# Sheet.net
KiCad netlist of a schematic drawn in Altium Designer
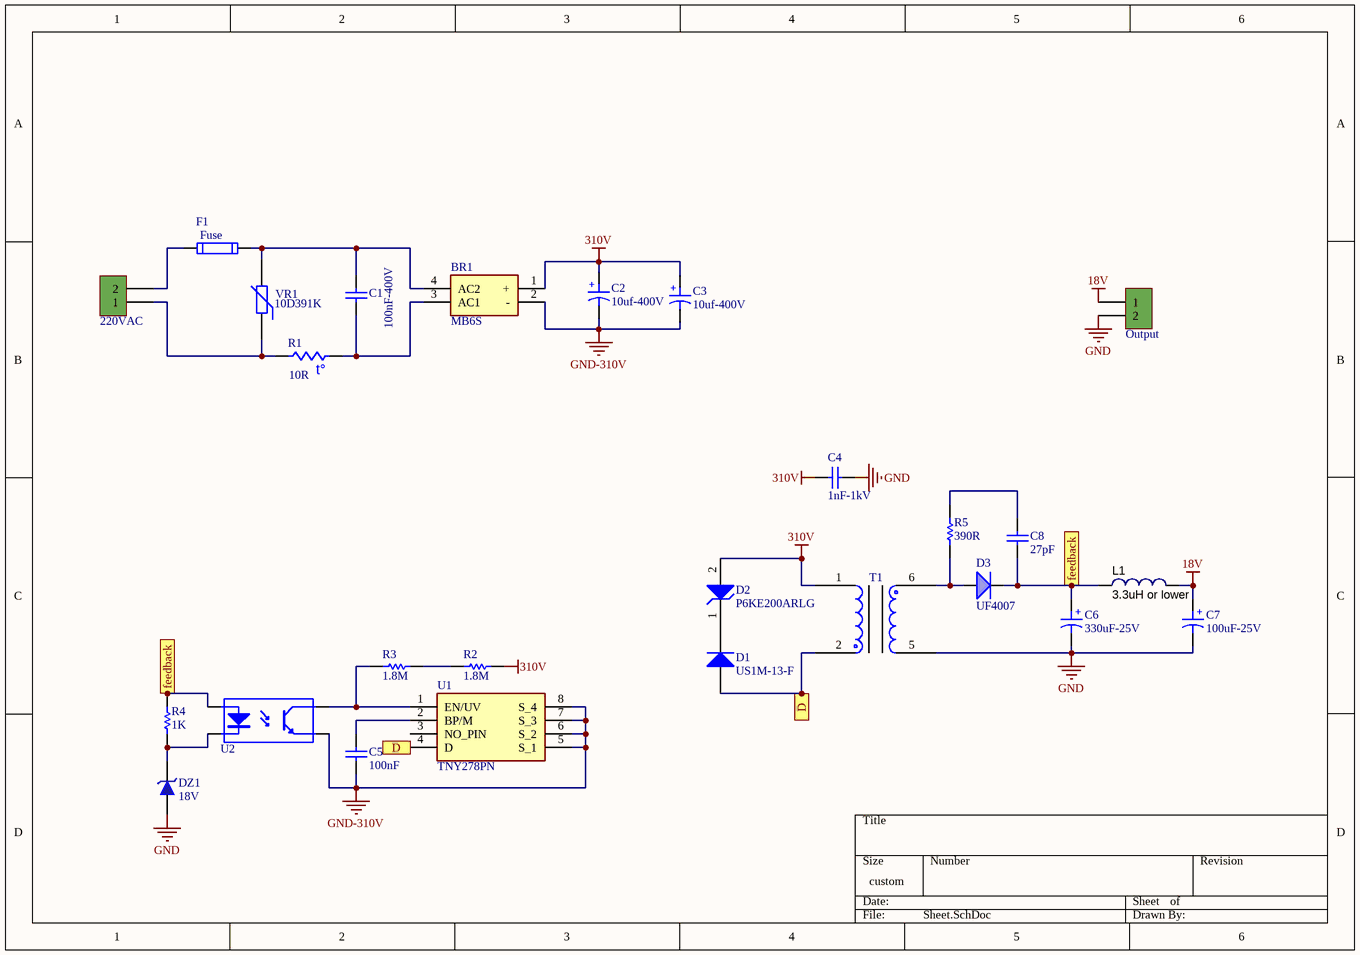
[diagram p0: Sheet.SchDoc]

(export (version "E")
  (design (tool "Eeschema 10.0.6"))
  (components
    (comp (ref "220VAC")
      (value "Phoenix 2 Pin")
      (footprint "Phoenix_2PIN_RA_P5.08mm")
      (libsource (lib "Connector") (part "Phoenix 2 Pin"))
    )
    (comp (ref "BR1")
      (value "MB6S")
      (footprint "SamacSys:SOP250P700X270-4N")
      (description "Bridge Rectifier")
      (libsource (lib "*") (part "MB6S"))
    )
    (comp (ref "C1")
      (value "100nF-400V")
      (footprint "Cap-100nF-400V")
      (description "CAP Ceramic Total")
      (fields (field (name "DESIGNER") "Ali Hafizi"))
      (libsource (lib "Altium") (part "CAP CERAMIC TOTAL SIZE"))
    )
    (comp (ref "C2")
      (value "10uf-400V")
      (footprint "Cap electrolitic radial 10x16-5")
      (description "Cap electrolitic radial")
      (fields (field (name "DESIGNER") "Abbas Basereh"))
      (libsource (lib "Schematic") (part "Cap ELECTROLITIC TOTAL SIZE"))
    )
    (comp (ref "C3")
      (value "10uf-400V")
      (footprint "Cap electrolitic radial 10x16-5")
      (description "Cap electrolitic radial")
      (fields (field (name "DESIGNER") "Abbas Basereh"))
      (libsource (lib "Schematic") (part "Cap ELECTROLITIC TOTAL SIZE"))
    )
    (comp (ref "C4")
      (value "1nF-1kV")
      (footprint "CAP1206")
      (description "TOTAL CAPACITOR SMD PACK")
      (fields (field (name "DESIGNER") "Abbas Basereh"))
      (libsource (lib "Altium") (part "CAP SMD PACKAGE"))
    )
    (comp (ref "C5")
      (value "100nF")
      (footprint "CAP805")
      (description "TOTAL CAPACITOR SMD PACK")
      (fields (field (name "DESIGNER") "Abbas Basereh"))
      (libsource (lib "Altium") (part "CAP SMD PACKAGE"))
    )
    (comp (ref "C6")
      (value "330uF-25V")
      (footprint "Cap electrolitic radial 8x12-3.5")
      (description "Cap electrolitic radial")
      (fields (field (name "DESIGNER") "Abbas Basereh"))
      (libsource (lib "Altium") (part "Cap ELECTROLITIC TOTAL SIZE"))
    )
    (comp (ref "C7")
      (value "100uF-25V")
      (footprint "Cap electrolitic radial 6.3x12-2.5")
      (description "Cap electrolitic radial")
      (fields (field (name "DESIGNER") "Abbas Basereh"))
      (libsource (lib "Altium") (part "Cap ELECTROLITIC TOTAL SIZE"))
    )
    (comp (ref "C8")
      (value "27pF")
      (footprint "CAP805")
      (description "TOTAL CAPACITOR SMD PACK")
      (fields (field (name "DESIGNER") "Abbas Basereh"))
      (libsource (lib "Altium") (part "CAP SMD PACKAGE"))
    )
    (comp (ref "D1")
      (value "US1M-13-F")
      (footprint "DIOD-SMA-2_A_V")
      (description "Ultra-Fast Rectifier, 1 A, 1.7 V, -65 to 150 degC, 2-Pin SMA, RoHS, Tape and Reel")
      (fields (field (name "MANUFACTURER") "Diodes Inc"))
      (libsource (lib "Altium Content Vault") (part "D-AK-2"))
    )
    (comp (ref "D2")
      (value "P6KE200ARLG")
      (footprint "ONSC-SURMETIC40-2-017AA-01")
      (description "600 W Peak Power Transient Voltage Suppressor, 2-Pin Surmetic(TM) 40, Pb-Free, Tape and Reel")
      (fields (field (name "MANUFACTURER") "On Semiconductor"))
      (libsource (lib "Altium Content Vault") (part "ONSC-K1A2-2"))
    )
    (comp (ref "D3")
      (value "UF4007")
      (footprint "DO-41")
      (description "Fast Switching Diodes")
      (fields
        (field (name "MANUFACTURER") "MIC GROUP RECTIFIERS")
        (field (name "MANUFACTURE PART #") "UF4007")
      )
      (libsource (lib "Diode") (part "UF4007"))
    )
    (comp (ref "DZ1")
      (value "18V")
      (footprint "SOD80, LL-34")
      (description "DIODE ZENER GENERAL")
      (fields (field (name "PUBLISHER") "Abbas Basereh"))
      (libsource (lib "Altium") (part "ZENER GENERAL DIODE"))
    )
    (comp (ref "F1")
      (value "FUSE_HOLDER_METAL")
      (footprint "FUSE_5X20MM_4PIN")
      (libsource (lib "Fuse") (part "FUSE METAL 4PIN"))
    )
    (comp (ref "L1")
      (value "3.3uH or lower")
      (footprint "Inductor SMD 3x3.2mm")
      (description "Inductor 4.7µH SMD 3x3.2mm")
      (fields (field (name "TOLERANCE") "±20%"))
      (libsource (lib "Altium") (part "Inductor 4.7µH SMD 3x3.2mm"))
    )
    (comp (ref "Output")
      (value "Phoenix 2 Pin")
      (footprint "Phoenix_2PIN_RA_P5.08mm")
      (libsource (lib "") (part "Phoenix 2 Pin_1"))
    )
    (comp (ref "R1")
      (value "10R")
      (footprint "NTC_9")
      (description "Thick film, SMD chip Resistor")
      (fields (field (name "MANUFACTURE PART #") "NTC10D-9") (field (name "TOLERANCE") "[20%]"))
      (libsource (lib "Resistor") (part "NTC10D-9"))
    )
    (comp (ref "R2")
      (value "1.8M")
      (footprint "RES0805_(2012X06L)")
      (description "TOTAL SMD RESISTOR PACK")
      (fields (field (name "DESIGNER") "Abbas Basereh"))
      (libsource (lib "Altium") (part "RES SMD PACKAGE"))
    )
    (comp (ref "R3")
      (value "1.8M")
      (footprint "RES0805_(2012X06L)")
      (description "TOTAL SMD RESISTOR PACK")
      (fields (field (name "DESIGNER") "Abbas Basereh"))
      (libsource (lib "Altium") (part "RES SMD PACKAGE"))
    )
    (comp (ref "R4")
      (value "1K")
      (footprint "RES0805_(2012X06L)")
      (description "TOTAL SMD RESISTOR PACK")
      (fields (field (name "DESIGNER") "Abbas Basereh"))
      (libsource (lib "Altium") (part "RES SMD PACKAGE"))
    )
    (comp (ref "R5")
      (value "390R")
      (footprint "RES0805_(2012X06L)")
      (description "TOTAL SMD RESISTOR PACK")
      (fields (field (name "DESIGNER") "Abbas Basereh"))
      (libsource (lib "Altium") (part "RES SMD PACKAGE"))
    )
    (comp (ref "T1") (value "EE16-18V") (footprint "EE16-18V") (libsource (lib "EE16-18V") (part "EE16-18V")))
    (comp (ref "U1")
      (value "TNY278PN")
      (footprint "SamacSys:DIP762W56P254L958H406Q8N")
      (description "Integrated Circuit")
      (fields
        (field (name "MANUFACTURER_PART_NUMBER") "TNY274PN")
        (field (name "MOUSER PART NUMBER") "869-TNY274PN")
      )
      (libsource (lib "*") (part "TNY274PN"))
    )
    (comp (ref "U2")
      (value "PC817")
      (footprint "SOP4")
      (description "General Purpose Photocoupler")
      (libsource (lib "Peripheral") (part "PC817"))
    )
    (comp (ref "VR1")
      (value "10D391K")
      (footprint "10D XXX")
      (description "VARISTORS")
      (fields
        (field (name "MANUFACTURER") "china-canada-philipina")
        (field (name "DESIGNER") "Abbas Basereh")
        (field (name "PUBLISHER") "ABBAS BASEREH")
      )
      (libsource (lib "Schematic") (part "VARISTOR (VDR)"))
    )
  )
  (nets
    (net (code "1") (name "/D") (class "Default")
      (node (ref "D1") (pin "1") (pinfunction "A_1") (pintype "passive"))
      (node (ref "T1") (pin "2") (pinfunction "2_2") (pintype "passive"))
      (node (ref "U1") (pin "4") (pinfunction "D_4") (pintype "passive"))
    )
    (net (code "2") (name "/feedback") (class "Default")
      (node (ref "C6") (pin "1") (pinfunction "1_1") (pintype "passive"))
      (node (ref "C8") (pin "1") (pinfunction "1_1") (pintype "passive"))
      (node (ref "D3") (pin "2") (pinfunction "CATHODE_2") (pintype "passive"))
      (node (ref "L1") (pin "1") (pinfunction "1_1") (pintype "passive"))
      (node (ref "R4") (pin "2") (pinfunction "2_2") (pintype "passive"))
      (node (ref "U2") (pin "1") (pinfunction "A_1") (pintype "passive"))
    )
    (net (code "3") (name "18V") (class "Default")
      (node (ref "C7") (pin "1") (pinfunction "1_1") (pintype "passive"))
      (node (ref "L1") (pin "2") (pinfunction "2_2") (pintype "passive"))
      (node (ref "Output") (pin "1") (pinfunction "1_1") (pintype "passive"))
    )
    (net (code "4") (name "310V") (class "Default")
      (node (ref "BR1") (pin "1") (pinfunction "+_1") (pintype "passive"))
      (node (ref "C2") (pin "1") (pinfunction "1_1") (pintype "passive"))
      (node (ref "C3") (pin "1") (pinfunction "1_1") (pintype "passive"))
      (node (ref "C4") (pin "2") (pinfunction "2_2") (pintype "passive"))
      (node (ref "D2") (pin "2") (pinfunction "A_2") (pintype "passive"))
      (node (ref "R2") (pin "2") (pinfunction "2_2") (pintype "passive"))
      (node (ref "T1") (pin "1") (pinfunction "1_1") (pintype "passive"))
    )
    (net (code "5") (name "GND") (class "Default")
      (node (ref "C4") (pin "1") (pinfunction "1_1") (pintype "passive"))
      (node (ref "C6") (pin "2") (pinfunction "2_2") (pintype "passive"))
      (node (ref "C7") (pin "2") (pinfunction "2_2") (pintype "passive"))
      (node (ref "DZ1") (pin "1") (pintype "passive"))
      (node (ref "Output") (pin "2") (pinfunction "2_2") (pintype "passive"))
      (node (ref "T1") (pin "5") (pinfunction "5_5") (pintype "passive"))
    )
    (net (code "6") (name "GND-310V") (class "Default")
      (node (ref "BR1") (pin "2") (pinfunction "-_2") (pintype "passive"))
      (node (ref "C2") (pin "2") (pinfunction "2_2") (pintype "passive"))
      (node (ref "C3") (pin "2") (pinfunction "2_2") (pintype "passive"))
      (node (ref "C5") (pin "1") (pinfunction "1_1") (pintype "passive"))
      (node (ref "U1") (pin "5") (pinfunction "S_1_5") (pintype "passive"))
      (node (ref "U1") (pin "6") (pinfunction "S_2_6") (pintype "passive"))
      (node (ref "U1") (pin "7") (pinfunction "S_3_7") (pintype "passive"))
      (node (ref "U1") (pin "8") (pinfunction "S_4_8") (pintype "passive"))
      (node (ref "U2") (pin "3") (pinfunction "E_3") (pintype "passive"))
    )
    (net (code "7") (name "Net-(220VAC-Pad1)") (class "Default")
      (node (ref "220VAC") (pin "1") (pinfunction "1_1") (pintype "passive"))
      (node (ref "R1") (pin "1") (pinfunction "1_1") (pintype "passive"))
      (node (ref "VR1") (pin "1") (pinfunction "1_1") (pintype "passive"))
    )
    (net (code "8") (name "Net-(220VAC-Pad2)") (class "Default")
      (node (ref "220VAC") (pin "2") (pinfunction "2_2") (pintype "passive"))
      (node (ref "F1") (pin "1") (pinfunction "1_1") (pintype "passive"))
    )
    (net (code "9") (name "Net-(BR1-AC1)") (class "Default")
      (node (ref "BR1") (pin "3") (pinfunction "AC1_3") (pintype "passive"))
      (node (ref "C1") (pin "2") (pinfunction "2_2") (pintype "passive"))
      (node (ref "R1") (pin "2") (pinfunction "2_2") (pintype "passive"))
    )
    (net (code "10") (name "Net-(BR1-AC2)") (class "Default")
      (node (ref "BR1") (pin "4") (pinfunction "AC2_4") (pintype "passive"))
      (node (ref "C1") (pin "1") (pinfunction "1_1") (pintype "passive"))
      (node (ref "F1") (pin "2") (pinfunction "2_2") (pintype "passive"))
      (node (ref "VR1") (pin "2") (pinfunction "2_2") (pintype "passive"))
    )
    (net (code "11") (name "Net-(C8-Pad2)") (class "Default")
      (node (ref "C8") (pin "2") (pinfunction "2_2") (pintype "passive"))
      (node (ref "R5") (pin "2") (pinfunction "2_2") (pintype "passive"))
    )
    (net (code "12") (name "Net-(D1-K)") (class "Default")
      (node (ref "D1") (pin "2") (pinfunction "K_2") (pintype "passive"))
      (node (ref "D2") (pin "1") (pinfunction "K_1") (pintype "passive"))
    )
    (net (code "13") (name "Net-(D3-ANODE)") (class "Default")
      (node (ref "D3") (pin "1") (pinfunction "ANODE_1") (pintype "passive"))
      (node (ref "R5") (pin "1") (pinfunction "1_1") (pintype "passive"))
      (node (ref "T1") (pin "6") (pinfunction "6_6") (pintype "passive"))
    )
    (net (code "14") (name "Net-(R2-Pad1)") (class "Default")
      (node (ref "R2") (pin "1") (pinfunction "1_1") (pintype "passive"))
      (node (ref "R3") (pin "2") (pinfunction "2_2") (pintype "passive"))
    )
    (net (code "15") (name "Net-(U1-BP{slash}M)") (class "Default")
      (node (ref "C5") (pin "2") (pinfunction "2_2") (pintype "passive"))
      (node (ref "U1") (pin "2") (pinfunction "BP/M_2") (pintype "passive"))
    )
    (net (code "16") (name "Net-(U1-EN{slash}UV)") (class "Default")
      (node (ref "R3") (pin "1") (pinfunction "1_1") (pintype "passive"))
      (node (ref "U1") (pin "1") (pinfunction "EN/UV_1") (pintype "passive"))
      (node (ref "U2") (pin "4") (pinfunction "C_4") (pintype "passive"))
    )
    (net (code "17") (name "Net-(U2-K)") (class "Default")
      (node (ref "DZ1") (pin "2") (pintype "passive"))
      (node (ref "R4") (pin "1") (pinfunction "1_1") (pintype "passive"))
      (node (ref "U2") (pin "2") (pinfunction "K_2") (pintype "passive"))
    )
    (net (code "18") (name "unconnected-(U1-NO_PIN-Pad3)") (class "Default")
      (node (ref "U1") (pin "3") (pinfunction "NO_PIN_3") (pintype "passive"))
    )
  )
)
